# 08_-FPGA_Bank_1_Interface.net
KiCad netlist of a schematic drawn in Altium Designer
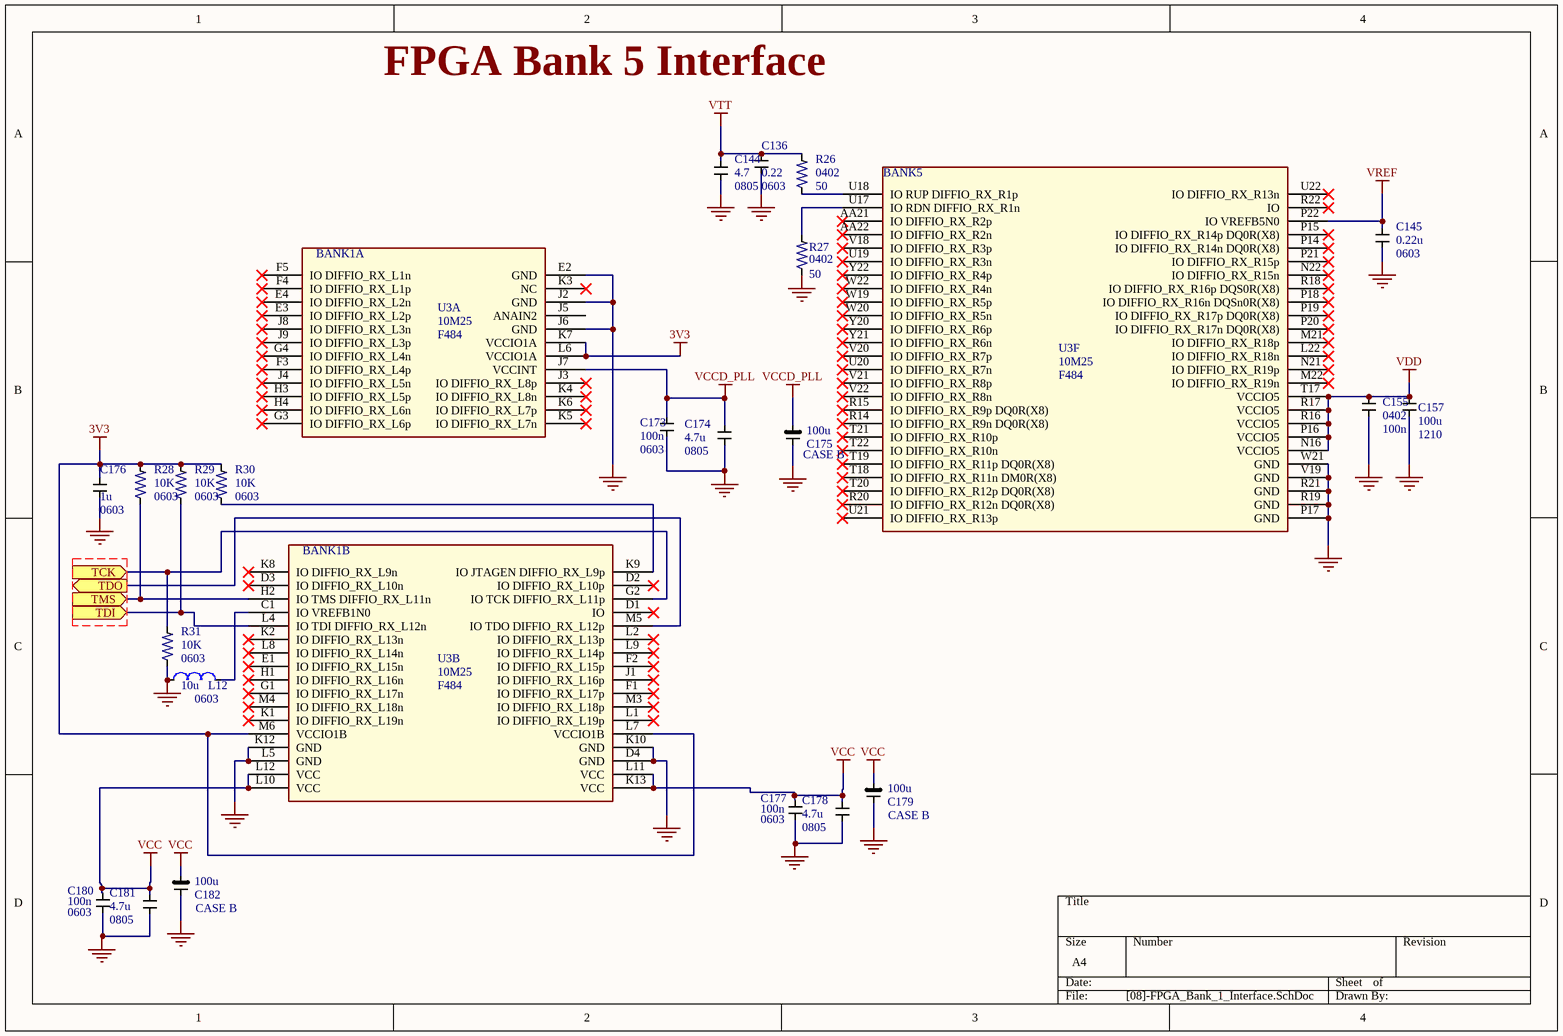
[diagram p0: [08]-FPGA_Bank_1_Interface.SchDoc]

(export (version "E")
  (design (tool "Eeschema 10.0.6"))
  (components
    (comp (ref "C136")
      (value "0.22")
      (footprint "*0603")
      (fields (field (name "PCB LAYER:") "0603"))
      (libsource (lib "0603YC105KAT2A") (part "Component_1"))
    )
    (comp (ref "C144")
      (value "4.7")
      (footprint "*CAPC2013X140N")
      (fields (field (name "PCB PACKAGE") "0805"))
      (libsource (lib "08053D475KAT2A") (part "Component_1"))
    )
    (comp (ref "C145")
      (value "0.22u")
      (footprint "*0603")
      (fields (field (name "PCB LAYER:") "0603"))
      (libsource (lib "0603YC105KAT2A") (part "Component_1"))
    )
    (comp (ref "C155")
      (value "100n")
      (fields (field (name "ALTIUM_UNNAMED_1") "0402"))
      (libsource (lib "04023C104KAT2A") (part "Component_1"))
    )
    (comp (ref "C157")
      (value "100u")
      (footprint "CAPC3225X28N")
      (fields (field (name "PCB PACKAGE TYPE") "1210"))
      (libsource (lib "1210") (part "Component_1"))
    )
    (comp (ref "C173")
      (value "100n")
      (footprint "*0603")
      (fields (field (name "PCB LAYER:") "0603"))
      (libsource (lib "0603YC105KAT2A") (part "Component_1"))
    )
    (comp (ref "C174")
      (value "4.7u")
      (fields (field (name "PCB FOOTPRINT") "0805"))
      (libsource (lib "06031C104KAT2A") (part "Component_1"))
    )
    (comp (ref "C175")
      (value "100u")
      (footprint "CAPC3529X21N")
      (fields (field (name "CASE") "CASE B"))
      (libsource (lib "TAJB107K006TNJ") (part "Component_1"))
    )
    (comp (ref "C176")
      (value "1u")
      (footprint "*0603")
      (fields (field (name "PCB LAYER:") "0603"))
      (libsource (lib "0603YC105KAT2A") (part "Component_1"))
    )
    (comp (ref "C177")
      (value "100n")
      (footprint "*0603")
      (fields (field (name "PCB LAYER:") "0603"))
      (libsource (lib "0603YC105KAT2A") (part "Component_1"))
    )
    (comp (ref "C178")
      (value "4.7u")
      (fields (field (name "PCB FOOTPRINT") "0805"))
      (libsource (lib "06031C104KAT2A") (part "Component_1"))
    )
    (comp (ref "C179")
      (value "100u")
      (footprint "CAPC3529X21N")
      (fields (field (name "CASE") "CASE B"))
      (libsource (lib "TAJB107K006TNJ") (part "Component_1"))
    )
    (comp (ref "C180")
      (value "100n")
      (footprint "*0603")
      (fields (field (name "PCB LAYER:") "0603"))
      (libsource (lib "0603YC105KAT2A") (part "Component_1"))
    )
    (comp (ref "C181")
      (value "4.7u")
      (fields (field (name "PCB FOOTPRINT") "0805"))
      (libsource (lib "06031C104KAT2A") (part "Component_1"))
    )
    (comp (ref "C182")
      (value "100u")
      (footprint "CAPC3529X21N")
      (fields (field (name "CASE") "CASE B"))
      (libsource (lib "TAJB107K006TNJ") (part "Component_1"))
    )
    (comp (ref "L12")
      (value "10u")
      (footprint "*INDC1608X95N")
      (fields (field (name "PCB LAYOUT:") "0603"))
      (libsource (lib "MLZ1608M100WTD25") (part "Component_1"))
    )
    (comp (ref "R26")
      (value "50")
      (footprint "*R0402")
      (description "Res Thin Film 0603 76.8 Ohm 0.1% 1/10W Â±15ppm/Â°C Molded SMD Paper T/R")
      (fields (field (name "PCB FOOTPRINT") "0402"))
      (libsource (lib "SMD-RES-100K-1_-1_16W_0402_") (part "RP73D1J76R8BTDG"))
    )
    (comp (ref "R27")
      (value "50")
      (footprint "*R0402")
      (description "Res Thin Film 0603 76.8 Ohm 0.1% 1/10W Â±15ppm/Â°C Molded SMD Paper T/R")
      (fields (field (name "PCB FOOTPRINT") "0402"))
      (libsource (lib "SMD-RES-100K-1_-1_16W_0402_") (part "RP73D1J76R8BTDG"))
    )
    (comp (ref "R28")
      (value "10K")
      (footprint "*0603")
      (description "Res Thin Film 0603 76.8 Ohm 0.1% 1/10W Â±15ppm/Â°C Molded SMD Paper T/R")
      (fields
        (field (name "MP") "RP73D1J76R8BTDG")
        (field (name "MF") "TE Connectivity / Holsworthy")
        (field (name "FOOT PRINT") "0603")
      )
      (libsource (lib "CRCW060347K0FKEA") (part "RP73D1J76R8BTDG"))
    )
    (comp (ref "R29")
      (value "10K")
      (footprint "*0603")
      (description "Res Thin Film 0603 76.8 Ohm 0.1% 1/10W Â±15ppm/Â°C Molded SMD Paper T/R")
      (fields
        (field (name "MP") "RP73D1J76R8BTDG")
        (field (name "MF") "TE Connectivity / Holsworthy")
        (field (name "FOOT PRINT") "0603")
      )
      (libsource (lib "CRCW060347K0FKEA") (part "RP73D1J76R8BTDG"))
    )
    (comp (ref "R30")
      (value "10K")
      (footprint "*0603")
      (description "Res Thin Film 0603 76.8 Ohm 0.1% 1/10W Â±15ppm/Â°C Molded SMD Paper T/R")
      (fields
        (field (name "MP") "RP73D1J76R8BTDG")
        (field (name "MF") "TE Connectivity / Holsworthy")
        (field (name "FOOT PRINT") "0603")
      )
      (libsource (lib "CRCW060347K0FKEA") (part "RP73D1J76R8BTDG"))
    )
    (comp (ref "R31")
      (value "10K")
      (footprint "*0603")
      (description "Res Thin Film 0603 76.8 Ohm 0.1% 1/10W Â±15ppm/Â°C Molded SMD Paper T/R")
      (fields
        (field (name "MP") "RP73D1J76R8BTDG")
        (field (name "MF") "TE Connectivity / Holsworthy")
        (field (name "FOOT PRINT") "0603")
      )
      (libsource (lib "CRCW060347K0FKEA") (part "RP73D1J76R8BTDG"))
    )
    (comp (ref "U3")
      (value "10M25")
      (footprint "*BGA484C100P22X22_2300X2300X200N")
      (fields (field (name "PART NO.") "10M25DAF484I7G") (field (name "PACKAGE TYPE") "F484"))
      (libsource (lib "10M25DAF484I7G") (part "Component_1"))
    )
  )
  (nets
    (net (code "1") (name "/TCK") (class "Default")
      (node (ref "R31") (pin "2") (pinfunction "2_2") (pintype "passive"))
      (node (ref "U3") (pin "G2") (pinfunction "IO_TCK_DIFFIO_RX_L11p_G2") (pintype "passive"))
    )
    (net (code "2") (name "/TDI") (class "Default")
      (node (ref "R29") (pin "1") (pinfunction "1_1") (pintype "passive"))
      (node (ref "U3") (pin "L4") (pinfunction "IO_TDI_DIFFIO_RX_L12n_L4") (pintype "passive"))
    )
    (net (code "3") (name "/TDO") (class "Default")
      (node (ref "U3") (pin "M5") (pinfunction "IO_TDO_DIFFIO_RX_L12p_M5") (pintype "passive"))
    )
    (net (code "4") (name "/TMS") (class "Default")
      (node (ref "R28") (pin "1") (pinfunction "1_1") (pintype "passive"))
      (node (ref "U3") (pin "H2") (pinfunction "IO_TMS_DIFFIO_RX_L11n_H2") (pintype "passive"))
    )
    (net (code "5") (name "3V3") (class "Default")
      (node (ref "C176") (pin "2") (pinfunction "2_2") (pintype "passive"))
      (node (ref "R28") (pin "2") (pinfunction "2_2") (pintype "passive"))
      (node (ref "R29") (pin "2") (pinfunction "2_2") (pintype "passive"))
      (node (ref "R30") (pin "2") (pinfunction "2_2") (pintype "passive"))
      (node (ref "U3") (pin "K7") (pinfunction "VCCIO1A_K7") (pintype "passive"))
      (node (ref "U3") (pin "L6") (pinfunction "VCCIO1A_L6") (pintype "passive"))
      (node (ref "U3") (pin "L7") (pinfunction "VCCIO1B_L7") (pintype "passive"))
      (node (ref "U3") (pin "M6") (pinfunction "VCCIO1B_M6") (pintype "passive"))
    )
    (net (code "6") (name "GND") (class "Default")
      (node (ref "C136") (pin "1") (pinfunction "1_1") (pintype "passive"))
      (node (ref "C144") (pin "1") (pinfunction "1_1") (pintype "passive"))
      (node (ref "C145") (pin "1") (pinfunction "1_1") (pintype "passive"))
      (node (ref "C155") (pin "1") (pinfunction "1_1") (pintype "passive"))
      (node (ref "C157") (pin "1") (pinfunction "1_1") (pintype "passive"))
      (node (ref "C173") (pin "1") (pinfunction "1_1") (pintype "passive"))
      (node (ref "C174") (pin "1") (pinfunction "1_1") (pintype "passive"))
      (node (ref "C175") (pin "2") (pinfunction "2_2") (pintype "passive"))
      (node (ref "C176") (pin "1") (pinfunction "1_1") (pintype "passive"))
      (node (ref "C177") (pin "1") (pinfunction "1_1") (pintype "passive"))
      (node (ref "C178") (pin "1") (pinfunction "1_1") (pintype "passive"))
      (node (ref "C179") (pin "2") (pinfunction "2_2") (pintype "passive"))
      (node (ref "C180") (pin "1") (pinfunction "1_1") (pintype "passive"))
      (node (ref "C181") (pin "1") (pinfunction "1_1") (pintype "passive"))
      (node (ref "C182") (pin "2") (pinfunction "2_2") (pintype "passive"))
      (node (ref "L12") (pin "1") (pinfunction "1_1") (pintype "passive"))
      (node (ref "R27") (pin "1") (pinfunction "1_1") (pintype "passive"))
      (node (ref "R31") (pin "1") (pinfunction "1_1") (pintype "passive"))
      (node (ref "U3") (pin "D4") (pinfunction "GND_D4") (pintype "passive"))
      (node (ref "U3") (pin "E2") (pinfunction "GND_E2") (pintype "passive"))
      (node (ref "U3") (pin "J2") (pinfunction "GND_J2") (pintype "passive"))
      (node (ref "U3") (pin "J6") (pinfunction "GND_J6") (pintype "passive"))
      (node (ref "U3") (pin "K10") (pinfunction "GND_K10") (pintype "passive"))
      (node (ref "U3") (pin "K12") (pinfunction "GND_K12") (pintype "passive"))
      (node (ref "U3") (pin "L5") (pinfunction "GND_L5") (pintype "passive"))
      (node (ref "U3") (pin "P17") (pinfunction "GND_P17") (pintype "passive"))
      (node (ref "U3") (pin "R19") (pinfunction "GND_R19") (pintype "passive"))
      (node (ref "U3") (pin "R21") (pinfunction "GND_R21") (pintype "passive"))
      (node (ref "U3") (pin "V19") (pinfunction "GND_V19") (pintype "passive"))
      (node (ref "U3") (pin "W21") (pinfunction "GND_W21") (pintype "passive"))
    )
    (net (code "7") (name "Net-(U3B-IO_JTAGEN_DIFFIO_RX_L9p)") (class "Default")
      (node (ref "R30") (pin "1") (pinfunction "1_1") (pintype "passive"))
      (node (ref "U3") (pin "K9") (pinfunction "IO_JTAGEN_DIFFIO_RX_L9p_K9") (pintype "passive"))
    )
    (net (code "8") (name "Net-(U3B-IO_VREFB1N0)") (class "Default")
      (node (ref "L12") (pin "2") (pinfunction "2_2") (pintype "passive"))
      (node (ref "U3") (pin "C1") (pinfunction "IO_VREFB1N0_C1") (pintype "passive"))
    )
    (net (code "9") (name "Net-(U3F-IO_RDN_DIFFIO_RX_R1n)") (class "Default")
      (node (ref "R27") (pin "2") (pinfunction "2_2") (pintype "passive"))
      (node (ref "U3") (pin "U17") (pinfunction "IO_RDN_DIFFIO_RX_R1n_U17") (pintype "passive"))
    )
    (net (code "10") (name "Net-(U3F-IO_RUP_DIFFIO_RX_R1p)") (class "Default")
      (node (ref "R26") (pin "1") (pinfunction "1_1") (pintype "passive"))
      (node (ref "U3") (pin "U18") (pinfunction "IO_RUP_DIFFIO_RX_R1p_U18") (pintype "passive"))
    )
    (net (code "11") (name "VCC") (class "Default")
      (node (ref "C177") (pin "2") (pinfunction "2_2") (pintype "passive"))
      (node (ref "C178") (pin "2") (pinfunction "2_2") (pintype "passive"))
      (node (ref "C179") (pin "1") (pinfunction "1_1") (pintype "passive"))
      (node (ref "C180") (pin "2") (pinfunction "2_2") (pintype "passive"))
      (node (ref "C181") (pin "2") (pinfunction "2_2") (pintype "passive"))
      (node (ref "C182") (pin "1") (pinfunction "1_1") (pintype "passive"))
      (node (ref "U3") (pin "K13") (pinfunction "VCC_K13") (pintype "passive"))
      (node (ref "U3") (pin "L10") (pinfunction "VCC_L10") (pintype "passive"))
      (node (ref "U3") (pin "L11") (pinfunction "VCC_L11") (pintype "passive"))
      (node (ref "U3") (pin "L12") (pinfunction "VCC_L12") (pintype "passive"))
    )
    (net (code "12") (name "VCCD_PLL") (class "Default")
      (node (ref "C173") (pin "2") (pinfunction "2_2") (pintype "passive"))
      (node (ref "C174") (pin "2") (pinfunction "2_2") (pintype "passive"))
      (node (ref "C175") (pin "1") (pinfunction "1_1") (pintype "passive"))
      (node (ref "U3") (pin "J7") (pinfunction "VCCINT_J7") (pintype "passive"))
    )
    (net (code "13") (name "VDD") (class "Default")
      (node (ref "C155") (pin "2") (pinfunction "2_2") (pintype "passive"))
      (node (ref "C157") (pin "2") (pinfunction "2_2") (pintype "passive"))
      (node (ref "U3") (pin "N16") (pinfunction "VCCIO5_N16") (pintype "passive"))
      (node (ref "U3") (pin "P16") (pinfunction "VCCIO5_P16") (pintype "passive"))
      (node (ref "U3") (pin "R16") (pinfunction "VCCIO5_R16") (pintype "passive"))
      (node (ref "U3") (pin "R17") (pinfunction "VCCIO5_R17") (pintype "passive"))
      (node (ref "U3") (pin "T17") (pinfunction "VCCIO5_T17") (pintype "passive"))
    )
    (net (code "14") (name "VREF") (class "Default")
      (node (ref "C145") (pin "2") (pinfunction "2_2") (pintype "passive"))
      (node (ref "U3") (pin "P22") (pinfunction "IO_VREFB5N0_P22") (pintype "passive"))
    )
    (net (code "15") (name "VTT") (class "Default")
      (node (ref "C136") (pin "2") (pinfunction "2_2") (pintype "passive"))
      (node (ref "C144") (pin "2") (pinfunction "2_2") (pintype "passive"))
      (node (ref "R26") (pin "2") (pinfunction "2_2") (pintype "passive"))
    )
    (net (code "16") (name "unconnected-(U3A-ANAIN2-PadJ5)") (class "Default")
      (node (ref "U3") (pin "J5") (pinfunction "ANAIN2_J5") (pintype "passive"))
    )
    (net (code "17") (name "unconnected-(U3A-IO_DIFFIO_RX_L1n-PadF5)") (class "Default")
      (node (ref "U3") (pin "F5") (pinfunction "IO_DIFFIO_RX_L1n_F5") (pintype "passive+no_connect"))
    )
    (net (code "18") (name "unconnected-(U3A-IO_DIFFIO_RX_L1p-PadF4)") (class "Default")
      (node (ref "U3") (pin "F4") (pinfunction "IO_DIFFIO_RX_L1p_F4") (pintype "passive+no_connect"))
    )
    (net (code "19") (name "unconnected-(U3A-IO_DIFFIO_RX_L2n-PadE4)") (class "Default")
      (node (ref "U3") (pin "E4") (pinfunction "IO_DIFFIO_RX_L2n_E4") (pintype "passive+no_connect"))
    )
    (net (code "20") (name "unconnected-(U3A-IO_DIFFIO_RX_L2p-PadE3)") (class "Default")
      (node (ref "U3") (pin "E3") (pinfunction "IO_DIFFIO_RX_L2p_E3") (pintype "passive+no_connect"))
    )
    (net (code "21") (name "unconnected-(U3A-IO_DIFFIO_RX_L3n-PadJ8)") (class "Default")
      (node (ref "U3") (pin "J8") (pinfunction "IO_DIFFIO_RX_L3n_J8") (pintype "passive+no_connect"))
    )
    (net (code "22") (name "unconnected-(U3A-IO_DIFFIO_RX_L3p-PadJ9)") (class "Default")
      (node (ref "U3") (pin "J9") (pinfunction "IO_DIFFIO_RX_L3p_J9") (pintype "passive+no_connect"))
    )
    (net (code "23") (name "unconnected-(U3A-IO_DIFFIO_RX_L4n-PadG4)") (class "Default")
      (node (ref "U3") (pin "G4") (pinfunction "IO_DIFFIO_RX_L4n_G4") (pintype "passive+no_connect"))
    )
    (net (code "24") (name "unconnected-(U3A-IO_DIFFIO_RX_L4p-PadF3)") (class "Default")
      (node (ref "U3") (pin "F3") (pinfunction "IO_DIFFIO_RX_L4p_F3") (pintype "passive+no_connect"))
    )
    (net (code "25") (name "unconnected-(U3A-IO_DIFFIO_RX_L5n-PadJ4)") (class "Default")
      (node (ref "U3") (pin "J4") (pinfunction "IO_DIFFIO_RX_L5n_J4") (pintype "passive+no_connect"))
    )
    (net (code "26") (name "unconnected-(U3A-IO_DIFFIO_RX_L5p-PadH3)") (class "Default")
      (node (ref "U3") (pin "H3") (pinfunction "IO_DIFFIO_RX_L5p_H3") (pintype "passive+no_connect"))
    )
    (net (code "27") (name "unconnected-(U3A-IO_DIFFIO_RX_L6n-PadH4)") (class "Default")
      (node (ref "U3") (pin "H4") (pinfunction "IO_DIFFIO_RX_L6n_H4") (pintype "passive+no_connect"))
    )
    (net (code "28") (name "unconnected-(U3A-IO_DIFFIO_RX_L6p-PadG3)") (class "Default")
      (node (ref "U3") (pin "G3") (pinfunction "IO_DIFFIO_RX_L6p_G3") (pintype "passive+no_connect"))
    )
    (net (code "29") (name "unconnected-(U3A-IO_DIFFIO_RX_L7n-PadK5)") (class "Default")
      (node (ref "U3") (pin "K5") (pinfunction "IO_DIFFIO_RX_L7n_K5") (pintype "passive+no_connect"))
    )
    (net (code "30") (name "unconnected-(U3A-IO_DIFFIO_RX_L7p-PadK6)") (class "Default")
      (node (ref "U3") (pin "K6") (pinfunction "IO_DIFFIO_RX_L7p_K6") (pintype "passive+no_connect"))
    )
    (net (code "31") (name "unconnected-(U3A-IO_DIFFIO_RX_L8n-PadK4)") (class "Default")
      (node (ref "U3") (pin "K4") (pinfunction "IO_DIFFIO_RX_L8n_K4") (pintype "passive+no_connect"))
    )
    (net (code "32") (name "unconnected-(U3A-IO_DIFFIO_RX_L8p-PadJ3)") (class "Default")
      (node (ref "U3") (pin "J3") (pinfunction "IO_DIFFIO_RX_L8p_J3") (pintype "passive+no_connect"))
    )
    (net (code "33") (name "unconnected-(U3A-NC-PadK3)") (class "Default")
      (node (ref "U3") (pin "K3") (pinfunction "NC_K3") (pintype "passive+no_connect"))
    )
    (net (code "34") (name "unconnected-(U3B-IO-PadD1)") (class "Default")
      (node (ref "U3") (pin "D1") (pinfunction "IO_D1") (pintype "passive+no_connect"))
    )
    (net (code "35") (name "unconnected-(U3B-IO_DIFFIO_RX_L9n-PadK8)") (class "Default")
      (node (ref "U3") (pin "K8") (pinfunction "IO_DIFFIO_RX_L9n_K8") (pintype "passive+no_connect"))
    )
    (net (code "36") (name "unconnected-(U3B-IO_DIFFIO_RX_L10n-PadD3)") (class "Default")
      (node (ref "U3") (pin "D3") (pinfunction "IO_DIFFIO_RX_L10n_D3") (pintype "passive+no_connect"))
    )
    (net (code "37") (name "unconnected-(U3B-IO_DIFFIO_RX_L10p-PadD2)") (class "Default")
      (node (ref "U3") (pin "D2") (pinfunction "IO_DIFFIO_RX_L10p_D2") (pintype "passive+no_connect"))
    )
    (net (code "38") (name "unconnected-(U3B-IO_DIFFIO_RX_L13n-PadK2)") (class "Default")
      (node (ref "U3") (pin "K2") (pinfunction "IO_DIFFIO_RX_L13n_K2") (pintype "passive+no_connect"))
    )
    (net (code "39") (name "unconnected-(U3B-IO_DIFFIO_RX_L13p-PadL2)") (class "Default")
      (node (ref "U3") (pin "L2") (pinfunction "IO_DIFFIO_RX_L13p_L2") (pintype "passive+no_connect"))
    )
    (net (code "40") (name "unconnected-(U3B-IO_DIFFIO_RX_L14n-PadL8)") (class "Default")
      (node (ref "U3") (pin "L8") (pinfunction "IO_DIFFIO_RX_L14n_L8") (pintype "passive+no_connect"))
    )
    (net (code "41") (name "unconnected-(U3B-IO_DIFFIO_RX_L14p-PadL9)") (class "Default")
      (node (ref "U3") (pin "L9") (pinfunction "IO_DIFFIO_RX_L14p_L9") (pintype "passive+no_connect"))
    )
    (net (code "42") (name "unconnected-(U3B-IO_DIFFIO_RX_L15n-PadE1)") (class "Default")
      (node (ref "U3") (pin "E1") (pinfunction "IO_DIFFIO_RX_L15n_E1") (pintype "passive+no_connect"))
    )
    (net (code "43") (name "unconnected-(U3B-IO_DIFFIO_RX_L15p-PadF2)") (class "Default")
      (node (ref "U3") (pin "F2") (pinfunction "IO_DIFFIO_RX_L15p_F2") (pintype "passive+no_connect"))
    )
    (net (code "44") (name "unconnected-(U3B-IO_DIFFIO_RX_L16n-PadH1)") (class "Default")
      (node (ref "U3") (pin "H1") (pinfunction "IO_DIFFIO_RX_L16n_H1") (pintype "passive+no_connect"))
    )
    (net (code "45") (name "unconnected-(U3B-IO_DIFFIO_RX_L16p-PadJ1)") (class "Default")
      (node (ref "U3") (pin "J1") (pinfunction "IO_DIFFIO_RX_L16p_J1") (pintype "passive+no_connect"))
    )
    (net (code "46") (name "unconnected-(U3B-IO_DIFFIO_RX_L17n-PadG1)") (class "Default")
      (node (ref "U3") (pin "G1") (pinfunction "IO_DIFFIO_RX_L17n_G1") (pintype "passive+no_connect"))
    )
    (net (code "47") (name "unconnected-(U3B-IO_DIFFIO_RX_L17p-PadF1)") (class "Default")
      (node (ref "U3") (pin "F1") (pinfunction "IO_DIFFIO_RX_L17p_F1") (pintype "passive+no_connect"))
    )
    (net (code "48") (name "unconnected-(U3B-IO_DIFFIO_RX_L18n-PadM4)") (class "Default")
      (node (ref "U3") (pin "M4") (pinfunction "IO_DIFFIO_RX_L18n_M4") (pintype "passive+no_connect"))
    )
    (net (code "49") (name "unconnected-(U3B-IO_DIFFIO_RX_L18p-PadM3)") (class "Default")
      (node (ref "U3") (pin "M3") (pinfunction "IO_DIFFIO_RX_L18p_M3") (pintype "passive+no_connect"))
    )
    (net (code "50") (name "unconnected-(U3B-IO_DIFFIO_RX_L19n-PadK1)") (class "Default")
      (node (ref "U3") (pin "K1") (pinfunction "IO_DIFFIO_RX_L19n_K1") (pintype "passive+no_connect"))
    )
    (net (code "51") (name "unconnected-(U3B-IO_DIFFIO_RX_L19p-PadL1)") (class "Default")
      (node (ref "U3") (pin "L1") (pinfunction "IO_DIFFIO_RX_L19p_L1") (pintype "passive+no_connect"))
    )
    (net (code "52") (name "unconnected-(U3F-IO-PadR22)") (class "Default")
      (node (ref "U3") (pin "R22") (pinfunction "IO_R22") (pintype "passive+no_connect"))
    )
    (net (code "53") (name "unconnected-(U3F-IO_DIFFIO_RX_R2n-PadAA22)") (class "Default")
      (node (ref "U3") (pin "AA22") (pinfunction "IO_DIFFIO_RX_R2n_AA22") (pintype "passive+no_connect"))
    )
    (net (code "54") (name "unconnected-(U3F-IO_DIFFIO_RX_R2p-PadAA21)") (class "Default")
      (node (ref "U3") (pin "AA21") (pinfunction "IO_DIFFIO_RX_R2p_AA21") (pintype "passive+no_connect"))
    )
    (net (code "55") (name "unconnected-(U3F-IO_DIFFIO_RX_R3n-PadU19)") (class "Default")
      (node (ref "U3") (pin "U19") (pinfunction "IO_DIFFIO_RX_R3n_U19") (pintype "passive+no_connect"))
    )
    (net (code "56") (name "unconnected-(U3F-IO_DIFFIO_RX_R3p-PadV18)") (class "Default")
      (node (ref "U3") (pin "V18") (pinfunction "IO_DIFFIO_RX_R3p_V18") (pintype "passive+no_connect"))
    )
    (net (code "57") (name "unconnected-(U3F-IO_DIFFIO_RX_R4n-PadW22)") (class "Default")
      (node (ref "U3") (pin "W22") (pinfunction "IO_DIFFIO_RX_R4n_W22") (pintype "passive+no_connect"))
    )
    (net (code "58") (name "unconnected-(U3F-IO_DIFFIO_RX_R4p-PadY22)") (class "Default")
      (node (ref "U3") (pin "Y22") (pinfunction "IO_DIFFIO_RX_R4p_Y22") (pintype "passive+no_connect"))
    )
    (net (code "59") (name "unconnected-(U3F-IO_DIFFIO_RX_R5n-PadW20)") (class "Default")
      (node (ref "U3") (pin "W20") (pinfunction "IO_DIFFIO_RX_R5n_W20") (pintype "passive+no_connect"))
    )
    (net (code "60") (name "unconnected-(U3F-IO_DIFFIO_RX_R5p-PadW19)") (class "Default")
      (node (ref "U3") (pin "W19") (pinfunction "IO_DIFFIO_RX_R5p_W19") (pintype "passive+no_connect"))
    )
    (net (code "61") (name "unconnected-(U3F-IO_DIFFIO_RX_R6n-PadY21)") (class "Default")
      (node (ref "U3") (pin "Y21") (pinfunction "IO_DIFFIO_RX_R6n_Y21") (pintype "passive+no_connect"))
    )
    (net (code "62") (name "unconnected-(U3F-IO_DIFFIO_RX_R6p-PadY20)") (class "Default")
      (node (ref "U3") (pin "Y20") (pinfunction "IO_DIFFIO_RX_R6p_Y20") (pintype "passive+no_connect"))
    )
    (net (code "63") (name "unconnected-(U3F-IO_DIFFIO_RX_R7n-PadU20)") (class "Default")
      (node (ref "U3") (pin "U20") (pinfunction "IO_DIFFIO_RX_R7n_U20") (pintype "passive+no_connect"))
    )
    (net (code "64") (name "unconnected-(U3F-IO_DIFFIO_RX_R7p-PadV20)") (class "Default")
      (node (ref "U3") (pin "V20") (pinfunction "IO_DIFFIO_RX_R7p_V20") (pintype "passive+no_connect"))
    )
    (net (code "65") (name "unconnected-(U3F-IO_DIFFIO_RX_R8n-PadV22)") (class "Default")
      (node (ref "U3") (pin "V22") (pinfunction "IO_DIFFIO_RX_R8n_V22") (pintype "passive+no_connect"))
    )
    (net (code "66") (name "unconnected-(U3F-IO_DIFFIO_RX_R8p-PadV21)") (class "Default")
      (node (ref "U3") (pin "V21") (pinfunction "IO_DIFFIO_RX_R8p_V21") (pintype "passive+no_connect"))
    )
    (net (code "67") (name "unconnected-(U3F-IO_DIFFIO_RX_R9n_DQ0R(X8)-PadR14)") (class "Default")
      (node (ref "U3") (pin "R14") (pinfunction "IO_DIFFIO_RX_R9n_DQ0R(X8)_R14") (pintype "passive+no_connect"))
    )
    (net (code "68") (name "unconnected-(U3F-IO_DIFFIO_RX_R9p_DQ0R(X8)-PadR15)") (class "Default")
      (node (ref "U3") (pin "R15") (pinfunction "IO_DIFFIO_RX_R9p_DQ0R(X8)_R15") (pintype "passive+no_connect"))
    )
    (net (code "69") (name "unconnected-(U3F-IO_DIFFIO_RX_R10n-PadT22)") (class "Default")
      (node (ref "U3") (pin "T22") (pinfunction "IO_DIFFIO_RX_R10n_T22") (pintype "passive+no_connect"))
    )
    (net (code "70") (name "unconnected-(U3F-IO_DIFFIO_RX_R10p-PadT21)") (class "Default")
      (node (ref "U3") (pin "T21") (pinfunction "IO_DIFFIO_RX_R10p_T21") (pintype "passive+no_connect"))
    )
    (net (code "71") (name "unconnected-(U3F-IO_DIFFIO_RX_R11n_DM0R(X8)-PadT18)") (class "Default")
      (node (ref "U3") (pin "T18") (pinfunction "IO_DIFFIO_RX_R11n_DM0R(X8)_T18") (pintype "passive+no_connect"))
    )
    (net (code "72") (name "unconnected-(U3F-IO_DIFFIO_RX_R11p_DQ0R(X8)-PadT19)") (class "Default")
      (node (ref "U3") (pin "T19") (pinfunction "IO_DIFFIO_RX_R11p_DQ0R(X8)_T19") (pintype "passive+no_connect"))
    )
    (net (code "73") (name "unconnected-(U3F-IO_DIFFIO_RX_R12n_DQ0R(X8)-PadR20)") (class "Default")
      (node (ref "U3") (pin "R20") (pinfunction "IO_DIFFIO_RX_R12n_DQ0R(X8)_R20") (pintype "passive+no_connect"))
    )
    (net (code "74") (name "unconnected-(U3F-IO_DIFFIO_RX_R12p_DQ0R(X8)-PadT20)") (class "Default")
      (node (ref "U3") (pin "T20") (pinfunction "IO_DIFFIO_RX_R12p_DQ0R(X8)_T20") (pintype "passive+no_connect"))
    )
    (net (code "75") (name "unconnected-(U3F-IO_DIFFIO_RX_R13n-PadU22)") (class "Default")
      (node (ref "U3") (pin "U22") (pinfunction "IO_DIFFIO_RX_R13n_U22") (pintype "passive+no_connect"))
    )
    (net (code "76") (name "unconnected-(U3F-IO_DIFFIO_RX_R13p-PadU21)") (class "Default")
      (node (ref "U3") (pin "U21") (pinfunction "IO_DIFFIO_RX_R13p_U21") (pintype "passive+no_connect"))
    )
    (net (code "77") (name "unconnected-(U3F-IO_DIFFIO_RX_R14n_DQ0R(X8)-PadP14)") (class "Default")
      (node (ref "U3") (pin "P14") (pinfunction "IO_DIFFIO_RX_R14n_DQ0R(X8)_P14") (pintype "passive+no_connect"))
    )
    (net (code "78") (name "unconnected-(U3F-IO_DIFFIO_RX_R14p_DQ0R(X8)-PadP15)") (class "Default")
      (node (ref "U3") (pin "P15") (pinfunction "IO_DIFFIO_RX_R14p_DQ0R(X8)_P15") (pintype "passive+no_connect"))
    )
    (net (code "79") (name "unconnected-(U3F-IO_DIFFIO_RX_R15n-PadN22)") (class "Default")
      (node (ref "U3") (pin "N22") (pinfunction "IO_DIFFIO_RX_R15n_N22") (pintype "passive+no_connect"))
    )
    (net (code "80") (name "unconnected-(U3F-IO_DIFFIO_RX_R15p-PadP21)") (class "Default")
      (node (ref "U3") (pin "P21") (pinfunction "IO_DIFFIO_RX_R15p_P21") (pintype "passive+no_connect"))
    )
    (net (code "81") (name "unconnected-(U3F-IO_DIFFIO_RX_R16n_DQSn0R(X8)-PadP18)") (class "Default")
      (node (ref "U3") (pin "P18") (pinfunction "IO_DIFFIO_RX_R16n_DQSn0R(X8)_P18") (pintype "passive+no_connect"))
    )
    (net (code "82") (name "unconnected-(U3F-IO_DIFFIO_RX_R16p_DQS0R(X8)-PadR18)") (class "Default")
      (node (ref "U3") (pin "R18") (pinfunction "IO_DIFFIO_RX_R16p_DQS0R(X8)_R18") (pintype "passive+no_connect"))
    )
    (net (code "83") (name "unconnected-(U3F-IO_DIFFIO_RX_R17n_DQ0R(X8)-PadP20)") (class "Default")
      (node (ref "U3") (pin "P20") (pinfunction "IO_DIFFIO_RX_R17n_DQ0R(X8)_P20") (pintype "passive+no_connect"))
    )
    (net (code "84") (name "unconnected-(U3F-IO_DIFFIO_RX_R17p_DQ0R(X8)-PadP19)") (class "Default")
      (node (ref "U3") (pin "P19") (pinfunction "IO_DIFFIO_RX_R17p_DQ0R(X8)_P19") (pintype "passive+no_connect"))
    )
    (net (code "85") (name "unconnected-(U3F-IO_DIFFIO_RX_R18n-PadL22)") (class "Default")
      (node (ref "U3") (pin "L22") (pinfunction "IO_DIFFIO_RX_R18n_L22") (pintype "passive+no_connect"))
    )
    (net (code "86") (name "unconnected-(U3F-IO_DIFFIO_RX_R18p-PadM21)") (class "Default")
      (node (ref "U3") (pin "M21") (pinfunction "IO_DIFFIO_RX_R18p_M21") (pintype "passive+no_connect"))
    )
    (net (code "87") (name "unconnected-(U3F-IO_DIFFIO_RX_R19n-PadM22)") (class "Default")
      (node (ref "U3") (pin "M22") (pinfunction "IO_DIFFIO_RX_R19n_M22") (pintype "passive+no_connect"))
    )
    (net (code "88") (name "unconnected-(U3F-IO_DIFFIO_RX_R19p-PadN21)") (class "Default")
      (node (ref "U3") (pin "N21") (pinfunction "IO_DIFFIO_RX_R19p_N21") (pintype "passive+no_connect"))
    )
  )
)
